# psu.net
KiCad netlist of a schematic drawn in Altium Designer
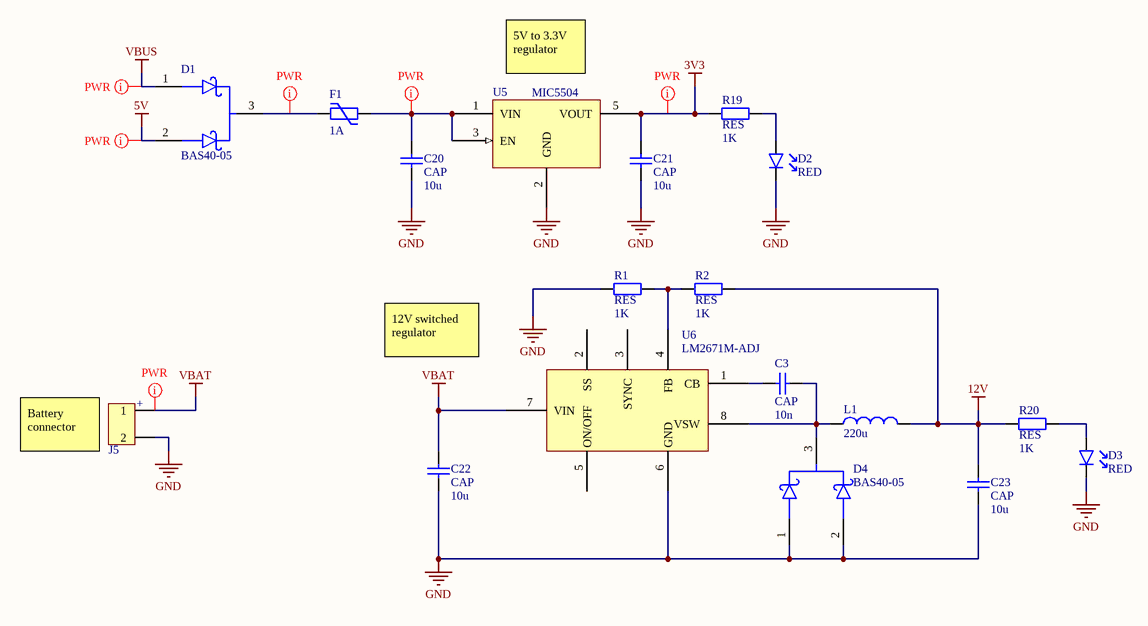
[diagram p0: psu.SchDoc]

(export (version "E")
  (design (tool "Eeschema 10.0.6"))
  (components
    (comp (ref "C3")
      (value "CAP")
      (footprint "CAPC1608X08M")
      (description "Capacitor")
      (fields (field (name "ALTIUM_VALUE") "10n") (field (name "PUBLISHER") "Altium Limited"))
      (libsource (lib "std") (part "CAP"))
    )
    (comp (ref "C20")
      (value "CAP")
      (footprint "CAPC2012X11M")
      (description "Capacitor")
      (fields (field (name "ALTIUM_VALUE") "10u") (field (name "PUBLISHER") "Altium Limited"))
      (libsource (lib "std") (part "CAP"))
    )
    (comp (ref "C21")
      (value "CAP")
      (footprint "CAPC2012X11M")
      (description "Capacitor")
      (fields (field (name "ALTIUM_VALUE") "10u") (field (name "PUBLISHER") "Altium Limited"))
      (libsource (lib "std") (part "CAP"))
    )
    (comp (ref "C22")
      (value "CAP")
      (footprint "CAPC3216X14M")
      (description "Capacitor")
      (fields (field (name "ALTIUM_VALUE") "10u") (field (name "PUBLISHER") "Altium Limited"))
      (libsource (lib "std") (part "CAP"))
    )
    (comp (ref "C23")
      (value "CAP")
      (footprint "CAPC3216X14M")
      (description "Capacitor")
      (fields (field (name "ALTIUM_VALUE") "10u") (field (name "PUBLISHER") "Altium Limited"))
      (libsource (lib "std") (part "CAP"))
    )
    (comp (ref "D1") (value "BAS40-05") (footprint "SOT23") (libsource (lib "std") (part "BAS40-05")))
    (comp (ref "D2") (value "RED") (footprint "RESC1608X06M") (libsource (lib "std") (part "LED")))
    (comp (ref "D3") (value "RED") (footprint "RESC1608X06M") (libsource (lib "std") (part "LED")))
    (comp (ref "D4") (value "BAS40-05") (footprint "SOT23") (libsource (lib "std") (part "BAS40-05")))
    (comp (ref "F1")
      (value "1A")
      (footprint "RESC3216X07M")
      (description "Polyfuse")
      (fields (field (name "Comment") "POLYFUSE") (field (name "PUBLISHER") "Altium Limited"))
      (libsource (lib "std") (part "POLYFUSE"))
    )
    (comp (ref "J5")
      (value "VBAT")
      (footprint "BAT_CNCTR")
      (description "2-pin batteri kontakt")
      (libsource (lib "std") (part "BAT_CNCTR"))
    )
    (comp (ref "L1")
      (value "220u")
      (footprint "INDC3924X34M")
      (description "Inductor")
      (fields (field (name "Comment") "IND") (field (name "PUBLISHER") "Altium Limited"))
      (libsource (lib "swreg") (part "AGV_IND"))
    )
    (comp (ref "R1")
      (value "RES")
      (footprint "RESC1608X06M")
      (description "Resistor")
      (fields (field (name "ALTIUM_VALUE") "1K") (field (name "PUBLISHER") "Altium Limited"))
      (libsource (lib "std") (part "RES"))
    )
    (comp (ref "R2")
      (value "RES")
      (footprint "RESC1608X06M")
      (description "Resistor")
      (fields (field (name "ALTIUM_VALUE") "1K") (field (name "PUBLISHER") "Altium Limited"))
      (libsource (lib "std") (part "RES"))
    )
    (comp (ref "R19")
      (value "RES")
      (footprint "RESC1608X06M")
      (description "Resistor")
      (fields (field (name "ALTIUM_VALUE") "1K") (field (name "PUBLISHER") "Altium Limited"))
      (libsource (lib "std") (part "RES"))
    )
    (comp (ref "R20")
      (value "RES")
      (footprint "RESC1608X06M")
      (description "Resistor")
      (fields (field (name "ALTIUM_VALUE") "1K") (field (name "PUBLISHER") "Altium Limited"))
      (libsource (lib "std") (part "RES"))
    )
    (comp (ref "U5") (value "MIC5504") (footprint "SOT23-5") (libsource (lib "std") (part "MIC5504-3.3")))
    (comp (ref "U6") (value "LM2671M-ADJ") (footprint "AGV_SO-8") (libsource (lib "swreg") (part "LM2671M")))
  )
  (nets
    (net (code "1") (name "3V3") (class "Default")
      (node (ref "C21") (pin "2") (pinfunction "2_2") (pintype "passive"))
      (node (ref "R19") (pin "1") (pinfunction "1_1") (pintype "passive"))
      (node (ref "U5") (pin "5") (pinfunction "VOUT_5") (pintype "power_in"))
    )
    (net (code "2") (name "5V") (class "Default")
      (node (ref "D1") (pin "2") (pinfunction "A2_2") (pintype "passive"))
    )
    (net (code "3") (name "12V") (class "Default")
      (node (ref "C23") (pin "2") (pinfunction "2_2") (pintype "passive"))
      (node (ref "L1") (pin "2") (pinfunction "2_2") (pintype "passive"))
      (node (ref "R2") (pin "2") (pinfunction "2_2") (pintype "passive"))
      (node (ref "R20") (pin "1") (pinfunction "1_1") (pintype "passive"))
    )
    (net (code "4") (name "GND") (class "Default")
      (node (ref "C20") (pin "1") (pinfunction "1_1") (pintype "passive"))
      (node (ref "C21") (pin "1") (pinfunction "1_1") (pintype "passive"))
      (node (ref "C22") (pin "1") (pinfunction "1_1") (pintype "passive"))
      (node (ref "C23") (pin "1") (pinfunction "1_1") (pintype "passive"))
      (node (ref "D2") (pin "2") (pinfunction "K_2") (pintype "passive"))
      (node (ref "D3") (pin "2") (pinfunction "K_2") (pintype "passive"))
      (node (ref "D4") (pin "1") (pinfunction "A1_1") (pintype "passive"))
      (node (ref "D4") (pin "2") (pinfunction "A2_2") (pintype "passive"))
      (node (ref "J5") (pin "2") (pinfunction "2_2") (pintype "passive"))
      (node (ref "R1") (pin "1") (pinfunction "1_1") (pintype "passive"))
      (node (ref "U5") (pin "2") (pinfunction "GND_2") (pintype "power_in"))
      (node (ref "U6") (pin "6") (pinfunction "GND_6") (pintype "power_in"))
    )
    (net (code "5") (name "Net-(D1-K)") (class "Default")
      (node (ref "D1") (pin "3") (pinfunction "K_3") (pintype "passive"))
      (node (ref "F1") (pin "2") (pinfunction "2_2") (pintype "passive"))
    )
    (net (code "6") (name "Net-(D2-A1)") (class "Default")
      (node (ref "D2") (pin "1") (pinfunction "A1_1") (pintype "passive"))
      (node (ref "R19") (pin "2") (pinfunction "2_2") (pintype "passive"))
    )
    (net (code "7") (name "Net-(D3-A1)") (class "Default")
      (node (ref "D3") (pin "1") (pinfunction "A1_1") (pintype "passive"))
      (node (ref "R20") (pin "2") (pinfunction "2_2") (pintype "passive"))
    )
    (net (code "8") (name "Net-(D4-K)") (class "Default")
      (node (ref "C3") (pin "1") (pinfunction "1_1") (pintype "passive"))
      (node (ref "D4") (pin "3") (pinfunction "K_3") (pintype "passive"))
      (node (ref "L1") (pin "1") (pinfunction "1_1") (pintype "passive"))
      (node (ref "U6") (pin "8") (pinfunction "VSW_8") (pintype "power_in"))
    )
    (net (code "9") (name "Net-(U5-EN)") (class "Default")
      (node (ref "C20") (pin "2") (pinfunction "2_2") (pintype "passive"))
      (node (ref "F1") (pin "1") (pinfunction "1_1") (pintype "passive"))
      (node (ref "U5") (pin "1") (pinfunction "VIN_1") (pintype "power_in"))
      (node (ref "U5") (pin "3") (pinfunction "EN_3") (pintype "input"))
    )
    (net (code "10") (name "Net-(U6-CB)") (class "Default")
      (node (ref "C3") (pin "2") (pinfunction "2_2") (pintype "passive"))
      (node (ref "U6") (pin "1") (pinfunction "CB_1") (pintype "power_in"))
    )
    (net (code "11") (name "Net-(U6-FB)") (class "Default")
      (node (ref "R1") (pin "2") (pinfunction "2_2") (pintype "passive"))
      (node (ref "R2") (pin "1") (pinfunction "1_1") (pintype "passive"))
      (node (ref "U6") (pin "4") (pinfunction "FB_4") (pintype "power_in"))
    )
    (net (code "12") (name "VBAT") (class "Default")
      (node (ref "C22") (pin "2") (pinfunction "2_2") (pintype "passive"))
      (node (ref "J5") (pin "1") (pinfunction "1_1") (pintype "passive"))
      (node (ref "U6") (pin "7") (pinfunction "VIN_7") (pintype "power_in"))
    )
    (net (code "13") (name "VBUS") (class "Default")
      (node (ref "D1") (pin "1") (pinfunction "A1_1") (pintype "passive"))
    )
    (net (code "14") (name "unconnected-(U6-ON{slash}OFF-Pad5)") (class "Default")
      (node (ref "U6") (pin "5") (pinfunction "ON/OFF_5") (pintype "passive"))
    )
    (net (code "15") (name "unconnected-(U6-SS-Pad2)") (class "Default")
      (node (ref "U6") (pin "2") (pinfunction "SS_2") (pintype "passive"))
    )
    (net (code "16") (name "unconnected-(U6-SYNC-Pad3)") (class "Default")
      (node (ref "U6") (pin "3") (pinfunction "SYNC_3") (pintype "passive"))
    )
  )
)
